# PHY_RJ45.net
KiCad netlist of a schematic drawn in Altium Designer
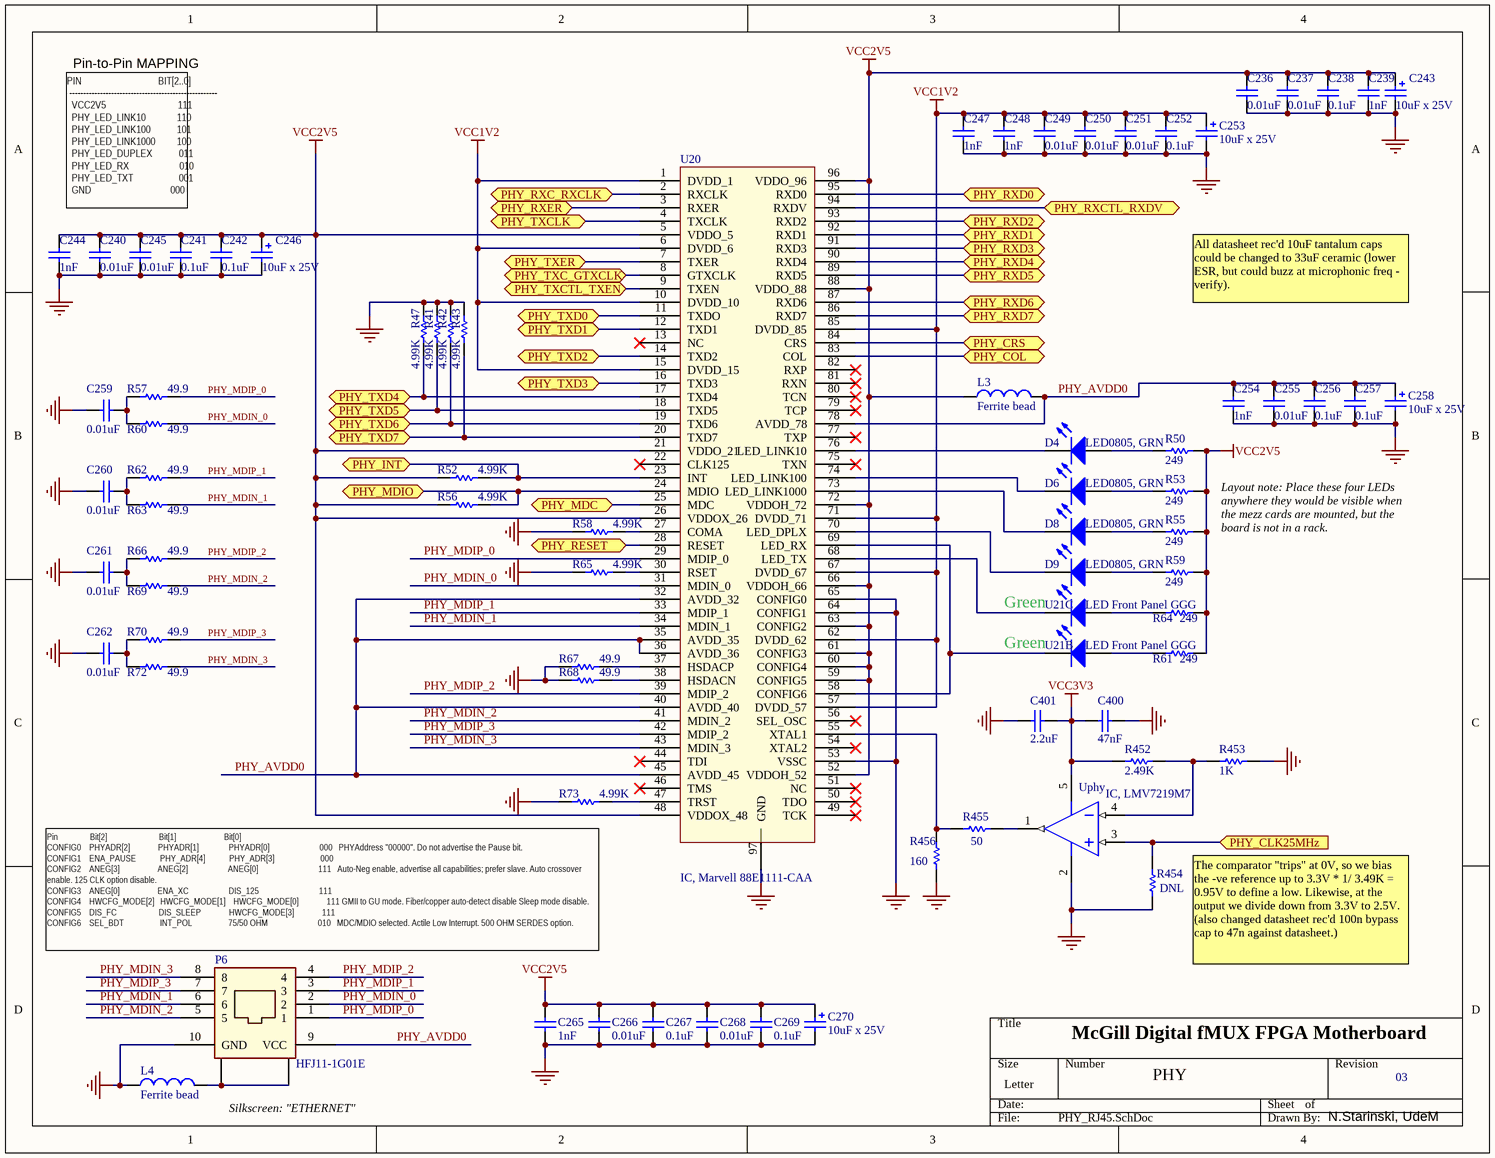
[diagram p0: PHY_RJ45.SchDoc]

(export (version "E")
  (design (tool "Eeschema 10.0.6"))
  (components
    (comp (ref "C236")
      (value "0.01uF")
      (footprint "CC1005-0402")
      (description "Capacitor (Semiconductor SIM Model)")
      (fields (field (name "PUBLISHER") "Altium Limited"))
      (libsource (lib "Miscellaneous Devices") (part "Cap Semi"))
    )
    (comp (ref "C237")
      (value "0.01uF")
      (footprint "CC1005-0402")
      (description "Capacitor (Semiconductor SIM Model)")
      (fields (field (name "PUBLISHER") "Altium Limited"))
      (libsource (lib "Miscellaneous Devices") (part "Cap Semi"))
    )
    (comp (ref "C238")
      (value "0.1uF")
      (footprint "CC1608-0603")
      (description "Capacitor (Semiconductor SIM Model)")
      (fields (field (name "PUBLISHER") "Altium Limited"))
      (libsource (lib "Miscellaneous Devices") (part "Cap Semi"))
    )
    (comp (ref "C239")
      (value "1nF")
      (footprint "CC1005-0402")
      (description "Capacitor (Semiconductor SIM Model)")
      (fields (field (name "PUBLISHER") "Altium Limited"))
      (libsource (lib "Miscellaneous Devices") (part "Cap Semi"))
    )
    (comp (ref "C240")
      (value "0.01uF")
      (footprint "CC1005-0402")
      (description "Capacitor (Semiconductor SIM Model)")
      (fields (field (name "PUBLISHER") "Altium Limited"))
      (libsource (lib "Miscellaneous Devices") (part "Cap Semi"))
    )
    (comp (ref "C241")
      (value "0.1uF")
      (footprint "CC1608-0603")
      (description "Capacitor (Semiconductor SIM Model)")
      (fields (field (name "PUBLISHER") "Altium Limited"))
      (libsource (lib "Miscellaneous Devices") (part "Cap Semi"))
    )
    (comp (ref "C242")
      (value "0.1uF")
      (footprint "CC1608-0603")
      (description "Capacitor (Semiconductor SIM Model)")
      (fields (field (name "PUBLISHER") "Altium Limited"))
      (libsource (lib "Miscellaneous Devices") (part "Cap Semi"))
    )
    (comp (ref "C243")
      (value "10uF x 25V")
      (footprint "TC6032-2412")
      (description "CAP POL B45197A5106K309")
      (fields (field (name "PUBLISHER") "Altium Limited"))
      (libsource (lib "Miscellaneous Devices 02") (part "Cap Pol3"))
    )
    (comp (ref "C244")
      (value "1nF")
      (footprint "CC1005-0402")
      (description "Capacitor (Semiconductor SIM Model)")
      (fields (field (name "PUBLISHER") "Altium Limited"))
      (libsource (lib "Miscellaneous Devices") (part "Cap Semi"))
    )
    (comp (ref "C245")
      (value "0.01uF")
      (footprint "CC1005-0402")
      (description "Capacitor (Semiconductor SIM Model)")
      (fields (field (name "PUBLISHER") "Altium Limited"))
      (libsource (lib "Miscellaneous Devices") (part "Cap Semi"))
    )
    (comp (ref "C246")
      (value "10uF x 25V")
      (footprint "TC6032-2412")
      (description "CAP POL B45197A5106K309")
      (fields (field (name "PUBLISHER") "Altium Limited"))
      (libsource (lib "Miscellaneous Devices 02") (part "Cap Pol3"))
    )
    (comp (ref "C247")
      (value "1nF")
      (footprint "CC1005-0402")
      (description "Capacitor (Semiconductor SIM Model)")
      (fields (field (name "PUBLISHER") "Altium Limited"))
      (libsource (lib "Miscellaneous Devices") (part "Cap Semi"))
    )
    (comp (ref "C248")
      (value "1nF")
      (footprint "CC1005-0402")
      (description "Capacitor (Semiconductor SIM Model)")
      (fields (field (name "PUBLISHER") "Altium Limited"))
      (libsource (lib "Miscellaneous Devices") (part "Cap Semi"))
    )
    (comp (ref "C249")
      (value "0.01uF")
      (footprint "CC1005-0402")
      (description "Capacitor (Semiconductor SIM Model)")
      (fields (field (name "PUBLISHER") "Altium Limited"))
      (libsource (lib "Miscellaneous Devices") (part "Cap Semi"))
    )
    (comp (ref "C250")
      (value "0.01uF")
      (footprint "CC1005-0402")
      (description "Capacitor (Semiconductor SIM Model)")
      (fields (field (name "PUBLISHER") "Altium Limited"))
      (libsource (lib "Miscellaneous Devices") (part "Cap Semi"))
    )
    (comp (ref "C251")
      (value "0.01uF")
      (footprint "CC1005-0402")
      (description "Capacitor (Semiconductor SIM Model)")
      (fields (field (name "PUBLISHER") "Altium Limited"))
      (libsource (lib "Miscellaneous Devices") (part "Cap Semi"))
    )
    (comp (ref "C252")
      (value "0.1uF")
      (footprint "CC1608-0603")
      (description "Capacitor (Semiconductor SIM Model)")
      (fields (field (name "PUBLISHER") "Altium Limited"))
      (libsource (lib "Miscellaneous Devices") (part "Cap Semi"))
    )
    (comp (ref "C253")
      (value "10uF x 25V")
      (footprint "TC6032-2412")
      (description "CAP POL B45197A5106K309")
      (fields (field (name "PUBLISHER") "Altium Limited"))
      (libsource (lib "Miscellaneous Devices 02") (part "Cap Pol3"))
    )
    (comp (ref "C254")
      (value "1nF")
      (footprint "CC1005-0402")
      (description "Capacitor (Semiconductor SIM Model)")
      (fields (field (name "PUBLISHER") "Altium Limited"))
      (libsource (lib "Miscellaneous Devices") (part "Cap Semi"))
    )
    (comp (ref "C255")
      (value "0.01uF")
      (footprint "CC1005-0402")
      (description "Capacitor (Semiconductor SIM Model)")
      (fields (field (name "PUBLISHER") "Altium Limited"))
      (libsource (lib "Miscellaneous Devices") (part "Cap Semi"))
    )
    (comp (ref "C256")
      (value "0.1uF")
      (footprint "CC1608-0603")
      (description "Capacitor (Semiconductor SIM Model)")
      (fields (field (name "PUBLISHER") "Altium Limited"))
      (libsource (lib "Miscellaneous Devices") (part "Cap Semi"))
    )
    (comp (ref "C257")
      (value "0.1uF")
      (footprint "CC1608-0603")
      (description "Capacitor (Semiconductor SIM Model)")
      (fields (field (name "PUBLISHER") "Altium Limited"))
      (libsource (lib "Miscellaneous Devices") (part "Cap Semi"))
    )
    (comp (ref "C258")
      (value "10uF x 25V")
      (footprint "TC6032-2412")
      (description "CAP POL B45197A5106K309")
      (fields (field (name "PUBLISHER") "Altium Limited"))
      (libsource (lib "Miscellaneous Devices 02") (part "Cap Pol3"))
    )
    (comp (ref "C259")
      (value "0.01uF")
      (footprint "CC1608-0603")
      (description "Capacitor (Semiconductor SIM Model)")
      (fields (field (name "PUBLISHER") "Altium Limited"))
      (libsource (lib "Miscellaneous Devices") (part "Cap Semi"))
    )
    (comp (ref "C260")
      (value "0.01uF")
      (footprint "CC1608-0603")
      (description "Capacitor (Semiconductor SIM Model)")
      (fields (field (name "PUBLISHER") "Altium Limited"))
      (libsource (lib "Miscellaneous Devices") (part "Cap Semi"))
    )
    (comp (ref "C261")
      (value "0.01uF")
      (footprint "CC1608-0603")
      (description "Capacitor (Semiconductor SIM Model)")
      (fields (field (name "PUBLISHER") "Altium Limited"))
      (libsource (lib "Miscellaneous Devices") (part "Cap Semi"))
    )
    (comp (ref "C262")
      (value "0.01uF")
      (footprint "CC1608-0603")
      (description "Capacitor (Semiconductor SIM Model)")
      (fields (field (name "PUBLISHER") "Altium Limited"))
      (libsource (lib "Miscellaneous Devices") (part "Cap Semi"))
    )
    (comp (ref "C265")
      (value "1nF")
      (footprint "CC1005-0402")
      (description "Capacitor (Semiconductor SIM Model)")
      (fields (field (name "PUBLISHER") "Altium Limited"))
      (libsource (lib "Miscellaneous Devices") (part "Cap Semi"))
    )
    (comp (ref "C266")
      (value "0.01uF")
      (footprint "CC1005-0402")
      (description "Capacitor (Semiconductor SIM Model)")
      (fields (field (name "PUBLISHER") "Altium Limited"))
      (libsource (lib "Miscellaneous Devices") (part "Cap Semi"))
    )
    (comp (ref "C267")
      (value "0.1uF")
      (footprint "CC1608-0603")
      (description "Capacitor (Semiconductor SIM Model)")
      (fields (field (name "PUBLISHER") "Altium Limited"))
      (libsource (lib "Miscellaneous Devices") (part "Cap Semi"))
    )
    (comp (ref "C268")
      (value "0.01uF")
      (footprint "CC1005-0402")
      (description "Capacitor (Semiconductor SIM Model)")
      (fields (field (name "PUBLISHER") "Altium Limited"))
      (libsource (lib "Miscellaneous Devices") (part "Cap Semi"))
    )
    (comp (ref "C269")
      (value "0.1uF")
      (footprint "CC1608-0603")
      (description "Capacitor (Semiconductor SIM Model)")
      (fields (field (name "PUBLISHER") "Altium Limited"))
      (libsource (lib "Miscellaneous Devices") (part "Cap Semi"))
    )
    (comp (ref "C270")
      (value "10uF x 25V")
      (footprint "TC6032-2412")
      (description "CAP POL B45197A5106K309")
      (fields (field (name "PUBLISHER") "Altium Limited"))
      (libsource (lib "Miscellaneous Devices 02") (part "Cap Pol3"))
    )
    (comp (ref "C400")
      (value "47nF")
      (footprint "CC1005-0402")
      (description "Capacitor (Semiconductor SIM Model)")
      (fields (field (name "PUBLISHER") "Altium Limited"))
      (libsource (lib "Miscellaneous Devices") (part "Cap Semi"))
    )
    (comp (ref "C401")
      (value "2.2uF")
      (footprint "CC3225-1210")
      (description "Capacitor (use 1206 footprint)")
      (fields (field (name "PUBLISHER") "Altium Limited"))
      (libsource (lib "Miscellaneous Devices") (part "Cap Semi"))
    )
    (comp (ref "D4")
      (value "LED0805, GRN")
      (footprint "SMD _LED")
      (description "LED 0805 LTST-C170GKT")
      (fields (field (name "PUBLISHER") "Altium Limited"))
      (libsource (lib "Miscellaneous Devices") (part "LED3"))
    )
    (comp (ref "D6")
      (value "LED0805, GRN")
      (footprint "SMD _LED")
      (description "LED 0805 LTST-C170GKT")
      (fields (field (name "PUBLISHER") "Altium Limited"))
      (libsource (lib "Miscellaneous Devices") (part "LED3"))
    )
    (comp (ref "D8")
      (value "LED0805, GRN")
      (footprint "SMD _LED")
      (description "LED 0805 LTST-C170GKT")
      (fields (field (name "PUBLISHER") "Altium Limited"))
      (libsource (lib "Miscellaneous Devices") (part "LED3"))
    )
    (comp (ref "D9")
      (value "LED0805, GRN")
      (footprint "SMD _LED")
      (description "LED 0805 LTST-C170GKT")
      (fields (field (name "PUBLISHER") "Altium Limited"))
      (libsource (lib "Miscellaneous Devices") (part "LED3"))
    )
    (comp (ref "L3")
      (value "Ferrite bead")
      (footprint "INDC2012-0805")
      (description "Inductor SM 0805")
      (fields (field (name "PUBLISHER") "Altium Limited"))
      (libsource (lib "Miscellaneous Devices") (part "Inductor"))
    )
    (comp (ref "L4")
      (value "Ferrite bead")
      (footprint "INDC2012-0805")
      (description "Inductor SM 0805")
      (fields (field (name "PUBLISHER") "Altium Limited"))
      (libsource (lib "Miscellaneous Devices 02") (part "Inductor"))
    )
    (comp (ref "P6")
      (value "HFJ11-1G01E")
      (footprint "HALO_RJ45")
      (description "Gigabit HALO RJ45")
      (libsource (lib "MyComp1") (part "HFJ11-1G01E"))
    )
    (comp (ref "R41")
      (value "4.99K")
      (footprint "CR1608-0603")
      (description "Resistor 0603")
      (fields (field (name "PUBLISHER") "Altium Limited"))
      (libsource (lib "Miscellaneous Devices") (part "Res Semi"))
    )
    (comp (ref "R42")
      (value "4.99K")
      (footprint "CR1608-0603")
      (description "Resistor 0603")
      (fields (field (name "PUBLISHER") "Altium Limited"))
      (libsource (lib "Miscellaneous Devices") (part "Res Semi"))
    )
    (comp (ref "R43")
      (value "4.99K")
      (footprint "CR1608-0603")
      (description "Resistor 0603")
      (fields (field (name "PUBLISHER") "Altium Limited"))
      (libsource (lib "Miscellaneous Devices") (part "Res Semi"))
    )
    (comp (ref "R47")
      (value "4.99K")
      (footprint "CR1608-0603")
      (description "Resistor 0603")
      (fields (field (name "PUBLISHER") "Altium Limited"))
      (libsource (lib "Miscellaneous Devices") (part "Res Semi"))
    )
    (comp (ref "R50")
      (value "249")
      (footprint "CR1608-0603")
      (description "Resistor 0603")
      (fields (field (name "PUBLISHER") "Altium Limited"))
      (libsource (lib "Miscellaneous Devices") (part "Res Semi"))
    )
    (comp (ref "R52")
      (value "4.99K")
      (footprint "CR1608-0603")
      (description "Resistor 0603")
      (fields (field (name "PUBLISHER") "Altium Limited"))
      (libsource (lib "Miscellaneous Devices") (part "Res Semi"))
    )
    (comp (ref "R53")
      (value "249")
      (footprint "CR1608-0603")
      (description "Resistor 0603")
      (fields (field (name "PUBLISHER") "Altium Limited"))
      (libsource (lib "Miscellaneous Devices") (part "Res Semi"))
    )
    (comp (ref "R55")
      (value "249")
      (footprint "CR1608-0603")
      (description "Resistor 0603")
      (fields (field (name "PUBLISHER") "Altium Limited"))
      (libsource (lib "Miscellaneous Devices") (part "Res Semi"))
    )
    (comp (ref "R56")
      (value "4.99K")
      (footprint "CR1608-0603")
      (description "Resistor 0603")
      (fields (field (name "PUBLISHER") "Altium Limited"))
      (libsource (lib "Miscellaneous Devices") (part "Res Semi"))
    )
    (comp (ref "R57")
      (value "49.9")
      (footprint "CR1608-0603")
      (description "Resistor 0603")
      (fields (field (name "PUBLISHER") "Altium Limited"))
      (libsource (lib "Miscellaneous Devices") (part "Res Semi"))
    )
    (comp (ref "R58")
      (value "4.99K")
      (footprint "CR1608-0603")
      (description "Resistor 0603")
      (fields (field (name "PUBLISHER") "Altium Limited"))
      (libsource (lib "Miscellaneous Devices") (part "Res Semi"))
    )
    (comp (ref "R59")
      (value "249")
      (footprint "CR1608-0603")
      (description "Resistor 0603")
      (fields (field (name "PUBLISHER") "Altium Limited"))
      (libsource (lib "Miscellaneous Devices") (part "Res Semi"))
    )
    (comp (ref "R60")
      (value "49.9")
      (footprint "CR1608-0603")
      (description "Resistor 0603")
      (fields (field (name "PUBLISHER") "Altium Limited"))
      (libsource (lib "Miscellaneous Devices") (part "Res Semi"))
    )
    (comp (ref "R61")
      (value "249")
      (footprint "CR1608-0603")
      (description "Resistor 0603")
      (fields (field (name "PUBLISHER") "Altium Limited"))
      (libsource (lib "Miscellaneous Devices") (part "Res Semi"))
    )
    (comp (ref "R62")
      (value "49.9")
      (footprint "CR1608-0603")
      (description "Resistor 0603")
      (fields (field (name "PUBLISHER") "Altium Limited"))
      (libsource (lib "Miscellaneous Devices") (part "Res Semi"))
    )
    (comp (ref "R63")
      (value "49.9")
      (footprint "CR1608-0603")
      (description "Resistor 0603")
      (fields (field (name "PUBLISHER") "Altium Limited"))
      (libsource (lib "Miscellaneous Devices") (part "Res Semi"))
    )
    (comp (ref "R64")
      (value "249")
      (footprint "CR1608-0603")
      (description "Resistor 0603")
      (fields (field (name "PUBLISHER") "Altium Limited"))
      (libsource (lib "Miscellaneous Devices") (part "Res Semi"))
    )
    (comp (ref "R65")
      (value "4.99K")
      (footprint "CR1608-0603")
      (description "Resistor 0603")
      (fields (field (name "PUBLISHER") "Altium Limited"))
      (libsource (lib "Miscellaneous Devices") (part "Res Semi"))
    )
    (comp (ref "R66")
      (value "49.9")
      (footprint "CR1608-0603")
      (description "Resistor 0603")
      (fields (field (name "PUBLISHER") "Altium Limited"))
      (libsource (lib "Miscellaneous Devices") (part "Res Semi"))
    )
    (comp (ref "R67")
      (value "49.9")
      (footprint "CR1608-0603")
      (description "Resistor 0603")
      (fields (field (name "PUBLISHER") "Altium Limited"))
      (libsource (lib "Miscellaneous Devices") (part "Res Semi"))
    )
    (comp (ref "R68")
      (value "49.9")
      (footprint "CR1608-0603")
      (description "Resistor 0603")
      (fields (field (name "PUBLISHER") "Altium Limited"))
      (libsource (lib "Miscellaneous Devices") (part "Res Semi"))
    )
    (comp (ref "R69")
      (value "49.9")
      (footprint "CR1608-0603")
      (description "Resistor 0603")
      (fields (field (name "PUBLISHER") "Altium Limited"))
      (libsource (lib "Miscellaneous Devices") (part "Res Semi"))
    )
    (comp (ref "R70")
      (value "49.9")
      (footprint "CR1608-0603")
      (description "Resistor 0603")
      (fields (field (name "PUBLISHER") "Altium Limited"))
      (libsource (lib "Miscellaneous Devices") (part "Res Semi"))
    )
    (comp (ref "R72")
      (value "49.9")
      (footprint "CR1608-0603")
      (description "Resistor 0603")
      (fields (field (name "PUBLISHER") "Altium Limited"))
      (libsource (lib "Miscellaneous Devices") (part "Res Semi"))
    )
    (comp (ref "R73")
      (value "4.99K")
      (footprint "CR1608-0603")
      (description "Resistor 0603")
      (fields (field (name "PUBLISHER") "Altium Limited"))
      (libsource (lib "Miscellaneous Devices") (part "Res Semi"))
    )
    (comp (ref "R452")
      (value "2.49K")
      (footprint "CR1608-0603")
      (description "Resistor 0603")
      (fields (field (name "PUBLISHER") "Altium Limited"))
      (libsource (lib "Miscellaneous Devices") (part "Res Semi"))
    )
    (comp (ref "R453")
      (value "1K")
      (footprint "CR1608-0603")
      (description "Resistor 0603")
      (fields (field (name "PUBLISHER") "Altium Limited"))
      (libsource (lib "Miscellaneous Devices") (part "Res Semi"))
    )
    (comp (ref "R454")
      (value "DNL")
      (footprint "CR1608-0603")
      (description "Semiconductor Resistor")
      (fields (field (name "PUBLISHER") "Altium Limited"))
      (libsource (lib "Miscellaneous Devices") (part "Res Semi"))
    )
    (comp (ref "R455")
      (value "50")
      (footprint "CR1608-0603")
      (description "Resistor 0603")
      (fields (field (name "PUBLISHER") "Altium Limited"))
      (libsource (lib "Miscellaneous Devices") (part "Res Semi"))
    )
    (comp (ref "R456")
      (value "160")
      (footprint "CR1608-0603")
      (description "Resistor 0603")
      (fields (field (name "PUBLISHER") "Altium Limited"))
      (libsource (lib "Miscellaneous Devices") (part "Res Semi"))
    )
    (comp (ref "U20")
      (value "IC, Marvell 88E1111-CAA")
      (footprint "BCC_96")
      (description "PHY 10/100/1000 Alaska Single-Port Gigabit Transceiver")
      (libsource (lib "MyComp1") (part "M88E1111-CAA"))
    )
    (comp (ref "U21")
      (value "LED Front Panel GGG")
      (footprint "LED_Tri_")
      (description "564-0200-222F")
      (libsource (lib "Miscellaneous Devices 02") (part "LED_Tri"))
    )
    (comp (ref "Uphy")
      (value "IC, LMV7219M7")
      (footprint "MAA05A")
      (description "Voltage Comparator")
      (libsource (lib "NSC Analog Comparator") (part "LMV7219"))
    )
  )
  (nets
    (net (code "1") (name "/PHY_AVDD0") (class "Default")
      (node (ref "C254") (pin "2") (pinfunction "2_2") (pintype "passive"))
      (node (ref "C255") (pin "2") (pinfunction "2_2") (pintype "passive"))
      (node (ref "C256") (pin "2") (pinfunction "2_2") (pintype "passive"))
      (node (ref "C257") (pin "2") (pinfunction "2_2") (pintype "passive"))
      (node (ref "C258") (pin "1") (pinfunction "1_1") (pintype "passive"))
      (node (ref "L3") (pin "2") (pinfunction "2_2") (pintype "passive"))
      (node (ref "P6") (pin "9") (pinfunction "VCC_9") (pintype "passive"))
      (node (ref "U20") (pin "32") (pinfunction "AVDD_32_32") (pintype "passive"))
      (node (ref "U20") (pin "35") (pinfunction "AVDD_35_35") (pintype "passive"))
      (node (ref "U20") (pin "36") (pinfunction "AVDD_36_36") (pintype "passive"))
      (node (ref "U20") (pin "40") (pinfunction "AVDD_40_40") (pintype "passive"))
      (node (ref "U20") (pin "45") (pinfunction "AVDD_45_45") (pintype "passive"))
      (node (ref "U20") (pin "78") (pinfunction "AVDD_78_78") (pintype "passive"))
    )
    (net (code "2") (name "/PHY_CLK25MHz") (class "Default")
      (node (ref "R454") (pin "2") (pinfunction "2_2") (pintype "passive"))
      (node (ref "Uphy") (pin "3") (pinfunction "IN+_3") (pintype "input"))
    )
    (net (code "3") (name "/PHY_COL") (class "Default")
      (node (ref "U20") (pin "83") (pinfunction "COL_83") (pintype "passive"))
    )
    (net (code "4") (name "/PHY_CRS") (class "Default")
      (node (ref "U20") (pin "84") (pinfunction "CRS_84") (pintype "passive"))
    )
    (net (code "5") (name "/PHY_INT") (class "Default")
      (node (ref "R52") (pin "2") (pinfunction "2_2") (pintype "passive"))
      (node (ref "U20") (pin "23") (pinfunction "INT_23") (pintype "passive"))
    )
    (net (code "6") (name "/PHY_MDC") (class "Default")
      (node (ref "U20") (pin "25") (pinfunction "MDC_25") (pintype "passive"))
    )
    (net (code "7") (name "/PHY_MDIN_0") (class "Default")
      (node (ref "P6") (pin "2") (pinfunction "2_2") (pintype "passive"))
      (node (ref "R60") (pin "2") (pinfunction "2_2") (pintype "passive"))
      (node (ref "U20") (pin "31") (pinfunction "MDIN_0_31") (pintype "passive"))
    )
    (net (code "8") (name "/PHY_MDIN_1") (class "Default")
      (node (ref "P6") (pin "6") (pinfunction "6_6") (pintype "passive"))
      (node (ref "R63") (pin "2") (pinfunction "2_2") (pintype "passive"))
      (node (ref "U20") (pin "34") (pinfunction "MDIN_1_34") (pintype "passive"))
    )
    (net (code "9") (name "/PHY_MDIN_2") (class "Default")
      (node (ref "P6") (pin "5") (pinfunction "5_5") (pintype "passive"))
      (node (ref "R69") (pin "2") (pinfunction "2_2") (pintype "passive"))
      (node (ref "U20") (pin "41") (pinfunction "MDIN_2_41") (pintype "passive"))
    )
    (net (code "10") (name "/PHY_MDIN_3") (class "Default")
      (node (ref "P6") (pin "8") (pinfunction "8_8") (pintype "passive"))
      (node (ref "R72") (pin "2") (pinfunction "2_2") (pintype "passive"))
      (node (ref "U20") (pin "43") (pinfunction "MDIN_3_43") (pintype "passive"))
    )
    (net (code "11") (name "/PHY_MDIO") (class "Default")
      (node (ref "R56") (pin "2") (pinfunction "2_2") (pintype "passive"))
      (node (ref "U20") (pin "24") (pinfunction "MDIO_24") (pintype "passive"))
    )
    (net (code "12") (name "/PHY_MDIP_0") (class "Default")
      (node (ref "P6") (pin "1") (pinfunction "1_1") (pintype "passive"))
      (node (ref "R57") (pin "2") (pinfunction "2_2") (pintype "passive"))
      (node (ref "U20") (pin "29") (pinfunction "MDIP_0_29") (pintype "passive"))
    )
    (net (code "13") (name "/PHY_MDIP_1") (class "Default")
      (node (ref "P6") (pin "3") (pinfunction "3_3") (pintype "passive"))
      (node (ref "R62") (pin "2") (pinfunction "2_2") (pintype "passive"))
      (node (ref "U20") (pin "33") (pinfunction "MDIP_1_33") (pintype "passive"))
    )
    (net (code "14") (name "/PHY_MDIP_2") (class "Default")
      (node (ref "P6") (pin "4") (pinfunction "4_4") (pintype "passive"))
      (node (ref "R66") (pin "2") (pinfunction "2_2") (pintype "passive"))
      (node (ref "U20") (pin "39") (pinfunction "MDIP_2_39") (pintype "passive"))
    )
    (net (code "15") (name "/PHY_MDIP_3") (class "Default")
      (node (ref "P6") (pin "7") (pinfunction "7_7") (pintype "passive"))
      (node (ref "R70") (pin "2") (pinfunction "2_2") (pintype "passive"))
      (node (ref "U20") (pin "42") (pinfunction "MDIP_2_42") (pintype "passive"))
    )
    (net (code "16") (name "/PHY_RESET") (class "Default")
      (node (ref "U20") (pin "28") (pinfunction "RESET_28") (pintype "passive"))
    )
    (net (code "17") (name "/PHY_RXCTL_RXDV") (class "Default")
      (node (ref "U20") (pin "94") (pinfunction "RXDV_94") (pintype "passive"))
    )
    (net (code "18") (name "/PHY_RXC_RXCLK") (class "Default")
      (node (ref "U20") (pin "2") (pinfunction "RXCLK_2") (pintype "passive"))
    )
    (net (code "19") (name "/PHY_RXD0") (class "Default")
      (node (ref "U20") (pin "95") (pinfunction "RXD0_95") (pintype "passive"))
    )
    (net (code "20") (name "/PHY_RXD1") (class "Default")
      (node (ref "U20") (pin "92") (pinfunction "RXD1_92") (pintype "passive"))
    )
    (net (code "21") (name "/PHY_RXD2") (class "Default")
      (node (ref "U20") (pin "93") (pinfunction "RXD2_93") (pintype "passive"))
    )
    (net (code "22") (name "/PHY_RXD3") (class "Default")
      (node (ref "U20") (pin "91") (pinfunction "RXD3_91") (pintype "passive"))
    )
    (net (code "23") (name "/PHY_RXD4") (class "Default")
      (node (ref "U20") (pin "90") (pinfunction "RXD4_90") (pintype "passive"))
    )
    (net (code "24") (name "/PHY_RXD5") (class "Default")
      (node (ref "U20") (pin "89") (pinfunction "RXD5_89") (pintype "passive"))
    )
    (net (code "25") (name "/PHY_RXD6") (class "Default")
      (node (ref "U20") (pin "87") (pinfunction "RXD6_87") (pintype "passive"))
    )
    (net (code "26") (name "/PHY_RXD7") (class "Default")
      (node (ref "U20") (pin "86") (pinfunction "RXD7_86") (pintype "passive"))
    )
    (net (code "27") (name "/PHY_RXER") (class "Default")
      (node (ref "U20") (pin "3") (pinfunction "RXER_3") (pintype "passive"))
    )
    (net (code "28") (name "/PHY_TXCLK") (class "Default")
      (node (ref "U20") (pin "4") (pinfunction "TXCLK_4") (pintype "passive"))
    )
    (net (code "29") (name "/PHY_TXCTL_TXEN") (class "Default")
      (node (ref "U20") (pin "9") (pinfunction "TXEN_9") (pintype "passive"))
    )
    (net (code "30") (name "/PHY_TXC_GTXCLK") (class "Default")
      (node (ref "U20") (pin "8") (pinfunction "GTXCLK_8") (pintype "passive"))
    )
    (net (code "31") (name "/PHY_TXD0") (class "Default")
      (node (ref "U20") (pin "11") (pinfunction "TXDO_11") (pintype "passive"))
    )
    (net (code "32") (name "/PHY_TXD1") (class "Default")
      (node (ref "U20") (pin "12") (pinfunction "TXD1_12") (pintype "passive"))
    )
    (net (code "33") (name "/PHY_TXD2") (class "Default")
      (node (ref "U20") (pin "14") (pinfunction "TXD2_14") (pintype "passive"))
    )
    (net (code "34") (name "/PHY_TXD3") (class "Default")
      (node (ref "U20") (pin "16") (pinfunction "TXD3_16") (pintype "passive"))
    )
    (net (code "35") (name "/PHY_TXD4") (class "Default")
      (node (ref "R47") (pin "1") (pinfunction "1_1") (pintype "passive"))
      (node (ref "U20") (pin "17") (pinfunction "TXD4_17") (pintype "passive"))
    )
    (net (code "36") (name "/PHY_TXD5") (class "Default")
      (node (ref "R41") (pin "1") (pinfunction "1_1") (pintype "passive"))
      (node (ref "U20") (pin "18") (pinfunction "TXD5_18") (pintype "passive"))
    )
    (net (code "37") (name "/PHY_TXD6") (class "Default")
      (node (ref "R42") (pin "1") (pinfunction "1_1") (pintype "passive"))
      (node (ref "U20") (pin "19") (pinfunction "TXD6_19") (pintype "passive"))
    )
    (net (code "38") (name "/PHY_TXD7") (class "Default")
      (node (ref "R43") (pin "1") (pinfunction "1_1") (pintype "passive"))
      (node (ref "U20") (pin "20") (pinfunction "TXD7_20") (pintype "passive"))
    )
    (net (code "39") (name "/PHY_TXER") (class "Default")
      (node (ref "U20") (pin "7") (pinfunction "TXER_7") (pintype "passive"))
    )
    (net (code "40") (name "GND") (class "Default")
      (node (ref "C236") (pin "1") (pinfunction "1_1") (pintype "passive"))
      (node (ref "C237") (pin "1") (pinfunction "1_1") (pintype "passive"))
      (node (ref "C238") (pin "1") (pinfunction "1_1") (pintype "passive"))
      (node (ref "C239") (pin "1") (pinfunction "1_1") (pintype "passive"))
      (node (ref "C240") (pin "1") (pinfunction "1_1") (pintype "passive"))
      (node (ref "C241") (pin "1") (pinfunction "1_1") (pintype "passive"))
      (node (ref "C242") (pin "1") (pinfunction "1_1") (pintype "passive"))
      (node (ref "C243") (pin "2") (pinfunction "2_2") (pintype "passive"))
      (node (ref "C244") (pin "1") (pinfunction "1_1") (pintype "passive"))
      (node (ref "C245") (pin "1") (pinfunction "1_1") (pintype "passive"))
      (node (ref "C246") (pin "2") (pinfunction "2_2") (pintype "passive"))
      (node (ref "C247") (pin "1") (pinfunction "1_1") (pintype "passive"))
      (node (ref "C248") (pin "1") (pinfunction "1_1") (pintype "passive"))
      (node (ref "C249") (pin "1") (pinfunction "1_1") (pintype "passive"))
      (node (ref "C250") (pin "1") (pinfunction "1_1") (pintype "passive"))
      (node (ref "C251") (pin "1") (pinfunction "1_1") (pintype "passive"))
      (node (ref "C252") (pin "1") (pinfunction "1_1") (pintype "passive"))
      (node (ref "C253") (pin "2") (pinfunction "2_2") (pintype "passive"))
      (node (ref "C254") (pin "1") (pinfunction "1_1") (pintype "passive"))
      (node (ref "C255") (pin "1") (pinfunction "1_1") (pintype "passive"))
      (node (ref "C256") (pin "1") (pinfunction "1_1") (pintype "passive"))
      (node (ref "C257") (pin "1") (pinfunction "1_1") (pintype "passive"))
      (node (ref "C258") (pin "2") (pinfunction "2_2") (pintype "passive"))
      (node (ref "C259") (pin "1") (pinfunction "1_1") (pintype "passive"))
      (node (ref "C260") (pin "1") (pinfunction "1_1") (pintype "passive"))
      (node (ref "C261") (pin "1") (pinfunction "1_1") (pintype "passive"))
      (node (ref "C262") (pin "1") (pinfunction "1_1") (pintype "passive"))
      (node (ref "C265") (pin "1") (pinfunction "1_1") (pintype "passive"))
      (node (ref "C266") (pin "1") (pinfunction "1_1") (pintype "passive"))
      (node (ref "C267") (pin "1") (pinfunction "1_1") (pintype "passive"))
      (node (ref "C268") (pin "1") (pinfunction "1_1") (pintype "passive"))
      (node (ref "C269") (pin "1") (pinfunction "1_1") (pintype "passive"))
      (node (ref "C270") (pin "2") (pinfunction "2_2") (pintype "passive"))
      (node (ref "C400") (pin "2") (pinfunction "2_2") (pintype "passive"))
      (node (ref "C401") (pin "2") (pinfunction "2_2") (pintype "passive"))
      (node (ref "L4") (pin "1") (pinfunction "1_1") (pintype "passive"))
      (node (ref "P6") (pin "10") (pinfunction "GND_10") (pintype "passive"))
      (node (ref "R41") (pin "2") (pinfunction "2_2") (pintype "passive"))
      (node (ref "R42") (pin "2") (pinfunction "2_2") (pintype "passive"))
      (node (ref "R43") (pin "2") (pinfunction "2_2") (pintype "passive"))
      (node (ref "R453") (pin "2") (pinfunction "2_2") (pintype "passive"))
      (node (ref "R454") (pin "1") (pinfunction "1_1") (pintype "passive"))
      (node (ref "R456") (pin "1") (pinfunction "1_1") (pintype "passive"))
      (node (ref "R47") (pin "2") (pinfunction "2_2") (pintype "passive"))
      (node (ref "R58") (pin "1") (pinfunction "1_1") (pintype "passive"))
      (node (ref "R65") (pin "1") (pinfunction "1_1") (pintype "passive"))
      (node (ref "R67") (pin "1") (pinfunction "1_1") (pintype "passive"))
      (node (ref "R68") (pin "1") (pinfunction "1_1") (pintype "passive"))
      (node (ref "R73") (pin "1") (pinfunction "1_1") (pintype "passive"))
      (node (ref "U20") (pin "53") (pinfunction "VSSC_53") (pintype "passive"))
      (node (ref "U20") (pin "64") (pinfunction "CONFIG1_64") (pintype "passive"))
      (node (ref "U20") (pin "65") (pinfunction "CONFIG0_65") (pintype "passive"))
      (node (ref "U20") (pin "97") (pinfunction "GND_97") (pintype "passive"))
      (node (ref "Uphy") (pin "2") (pinfunction "V-_2") (pintype "power_in"))
    )
    (net (code "41") (name "Net-(C259-Pad2)") (class "Default")
      (node (ref "C259") (pin "2") (pinfunction "2_2") (pintype "passive"))
      (node (ref "R57") (pin "1") (pinfunction "1_1") (pintype "passive"))
      (node (ref "R60") (pin "1") (pinfunction "1_1") (pintype "passive"))
    )
    (net (code "42") (name "Net-(C260-Pad2)") (class "Default")
      (node (ref "C260") (pin "2") (pinfunction "2_2") (pintype "passive"))
      (node (ref "R62") (pin "1") (pinfunction "1_1") (pintype "passive"))
      (node (ref "R63") (pin "1") (pinfunction "1_1") (pintype "passive"))
    )
    (net (code "43") (name "Net-(C261-Pad2)") (class "Default")
      (node (ref "C261") (pin "2") (pinfunction "2_2") (pintype "passive"))
      (node (ref "R66") (pin "1") (pinfunction "1_1") (pintype "passive"))
      (node (ref "R69") (pin "1") (pinfunction "1_1") (pintype "passive"))
    )
    (net (code "44") (name "Net-(C262-Pad2)") (class "Default")
      (node (ref "C262") (pin "2") (pinfunction "2_2") (pintype "passive"))
      (node (ref "R70") (pin "1") (pinfunction "1_1") (pintype "passive"))
      (node (ref "R72") (pin "1") (pinfunction "1_1") (pintype "passive"))
    )
    (net (code "45") (name "Net-(D4-A)") (class "Default")
      (node (ref "D4") (pin "1") (pinfunction "A_1") (pintype "passive"))
      (node (ref "R50") (pin "1") (pinfunction "1_1") (pintype "passive"))
    )
    (net (code "46") (name "Net-(D4-K)") (class "Default")
      (node (ref "D4") (pin "2") (pinfunction "K_2") (pintype "passive"))
      (node (ref "U20") (pin "76") (pinfunction "LED_LINK10_76") (pintype "passive"))
    )
    (net (code "47") (name "Net-(D6-A)") (class "Default")
      (node (ref "D6") (pin "1") (pinfunction "A_1") (pintype "passive"))
      (node (ref "R53") (pin "1") (pinfunction "1_1") (pintype "passive"))
    )
    (net (code "48") (name "Net-(D6-K)") (class "Default")
      (node (ref "D6") (pin "2") (pinfunction "K_2") (pintype "passive"))
      (node (ref "U20") (pin "74") (pinfunction "LED_LINK100_74") (pintype "passive"))
    )
    (net (code "49") (name "Net-(D8-A)") (class "Default")
      (node (ref "D8") (pin "1") (pinfunction "A_1") (pintype "passive"))
      (node (ref "R55") (pin "1") (pinfunction "1_1") (pintype "passive"))
    )
    (net (code "50") (name "Net-(D8-K)") (class "Default")
      (node (ref "D8") (pin "2") (pinfunction "K_2") (pintype "passive"))
      (node (ref "U20") (pin "73") (pinfunction "LED_LINK1000_73") (pintype "passive"))
    )
    (net (code "51") (name "Net-(D9-A)") (class "Default")
      (node (ref "D9") (pin "1") (pinfunction "A_1") (pintype "passive"))
      (node (ref "R59") (pin "1") (pinfunction "1_1") (pintype "passive"))
    )
    (net (code "52") (name "Net-(D9-K)") (class "Default")
      (node (ref "D9") (pin "2") (pinfunction "K_2") (pintype "passive"))
      (node (ref "U20") (pin "70") (pinfunction "LED_DPLX_70") (pintype "passive"))
    )
    (net (code "53") (name "Net-(L4-Pad2)") (class "Default")
      (node (ref "L4") (pin "2") (pinfunction "2_2") (pintype "passive"))
      (node (ref "P6") (pin "11") (pinfunction "GND_11") (pintype "power_in"))
      (node (ref "P6") (pin "12") (pinfunction "GND_12") (pintype "power_in"))
    )
    (net (code "54") (name "Net-(U20-COMA)") (class "Default")
      (node (ref "R58") (pin "2") (pinfunction "2_2") (pintype "passive"))
      (node (ref "U20") (pin "27") (pinfunction "COMA_27") (pintype "passive"))
    )
    (net (code "55") (name "Net-(U20-CONFIG6)") (class "Default")
      (node (ref "U20") (pin "58") (pinfunction "CONFIG6_58") (pintype "passive"))
      (node (ref "U20") (pin "69") (pinfunction "LED_RX_69") (pintype "passive"))
      (node (ref "U21") (pin "K2") (pinfunction "K_K2") (pintype "passive"))
    )
    (net (code "56") (name "Net-(U20-HSDACN)") (class "Default")
      (node (ref "R68") (pin "2") (pinfunction "2_2") (pintype "passive"))
      (node (ref "U20") (pin "38") (pinfunction "HSDACN_38") (pintype "passive"))
    )
    (net (code "57") (name "Net-(U20-HSDACP)") (class "Default")
      (node (ref "R67") (pin "2") (pinfunction "2_2") (pintype "passive"))
      (node (ref "U20") (pin "37") (pinfunction "HSDACP_37") (pintype "passive"))
    )
    (net (code "58") (name "Net-(U20-LED_TX)") (class "Default")
      (node (ref "U20") (pin "68") (pinfunction "LED_TX_68") (pintype "passive"))
      (node (ref "U21") (pin "K3") (pinfunction "K_K3") (pintype "passive"))
    )
    (net (code "59") (name "Net-(U20-RSET)") (class "Default")
      (node (ref "R65") (pin "2") (pinfunction "2_2") (pintype "passive"))
      (node (ref "U20") (pin "30") (pinfunction "RSET_30") (pintype "passive"))
    )
    (net (code "60") (name "Net-(U20-TRST)") (class "Default")
      (node (ref "R73") (pin "2") (pinfunction "2_2") (pintype "passive"))
      (node (ref "U20") (pin "47") (pinfunction "TRST_47") (pintype "passive"))
    )
    (net (code "61") (name "Net-(U20-XTAL1)") (class "Default")
      (node (ref "R455") (pin "1") (pinfunction "1_1") (pintype "passive"))
      (node (ref "R456") (pin "2") (pinfunction "2_2") (pintype "passive"))
      (node (ref "U20") (pin "55") (pinfunction "XTAL1_55") (pintype "passive"))
    )
    (net (code "62") (name "Net-(U21B-A)") (class "Default")
      (node (ref "R61") (pin "1") (pinfunction "1_1") (pintype "passive"))
      (node (ref "U21") (pin "A2") (pinfunction "A_A2") (pintype "passive"))
    )
    (net (code "63") (name "Net-(U21C-A)") (class "Default")
      (node (ref "R64") (pin "1") (pinfunction "1_1") (pintype "passive"))
      (node (ref "U21") (pin "A3") (pinfunction "A_A3") (pintype "passive"))
    )
    (net (code "64") (name "Net-(Uphy-IN-)") (class "Default")
      (node (ref "R452") (pin "2") (pinfunction "2_2") (pintype "passive"))
      (node (ref "R453") (pin "1") (pinfunction "1_1") (pintype "passive"))
      (node (ref "Uphy") (pin "4") (pinfunction "IN-_4") (pintype "input"))
    )
    (net (code "65") (name "Net-(Uphy-OUT)") (class "Default")
      (node (ref "R455") (pin "2") (pinfunction "2_2") (pintype "passive"))
      (node (ref "Uphy") (pin "1") (pinfunction "OUT_1") (pintype "output"))
    )
    (net (code "66") (name "VCC1V2") (class "Default")
      (node (ref "C247") (pin "2") (pinfunction "2_2") (pintype "passive"))
      (node (ref "C248") (pin "2") (pinfunction "2_2") (pintype "passive"))
      (node (ref "C249") (pin "2") (pinfunction "2_2") (pintype "passive"))
      (node (ref "C250") (pin "2") (pinfunction "2_2") (pintype "passive"))
      (node (ref "C251") (pin "2") (pinfunction "2_2") (pintype "passive"))
      (node (ref "C252") (pin "2") (pinfunction "2_2") (pintype "passive"))
      (node (ref "C253") (pin "1") (pinfunction "1_1") (pintype "passive"))
      (node (ref "U20") (pin "1") (pinfunction "DVDD_1_1") (pintype "passive"))
      (node (ref "U20") (pin "10") (pinfunction "DVDD_10_10") (pintype "passive"))
      (node (ref "U20") (pin "15") (pinfunction "DVDD_15_15") (pintype "passive"))
      (node (ref "U20") (pin "57") (pinfunction "DVDD_57_57") (pintype "passive"))
      (node (ref "U20") (pin "6") (pinfunction "DVDD_6_6") (pintype "passive"))
      (node (ref "U20") (pin "62") (pinfunction "DVDD_62_62") (pintype "passive"))
      (node (ref "U20") (pin "67") (pinfunction "DVDD_67_67") (pintype "passive"))
      (node (ref "U20") (pin "71") (pinfunction "DVDD_71_71") (pintype "passive"))
      (node (ref "U20") (pin "85") (pinfunction "DVDD_85_85") (pintype "passive"))
    )
    (net (code "67") (name "VCC2V5") (class "Default")
      (node (ref "C236") (pin "2") (pinfunction "2_2") (pintype "passive"))
      (node (ref "C237") (pin "2") (pinfunction "2_2") (pintype "passive"))
      (node (ref "C238") (pin "2") (pinfunction "2_2") (pintype "passive"))
      (node (ref "C239") (pin "2") (pinfunction "2_2") (pintype "passive"))
      (node (ref "C240") (pin "2") (pinfunction "2_2") (pintype "passive"))
      (node (ref "C241") (pin "2") (pinfunction "2_2") (pintype "passive"))
      (node (ref "C242") (pin "2") (pinfunction "2_2") (pintype "passive"))
      (node (ref "C243") (pin "1") (pinfunction "1_1") (pintype "passive"))
      (node (ref "C244") (pin "2") (pinfunction "2_2") (pintype "passive"))
      (node (ref "C245") (pin "2") (pinfunction "2_2") (pintype "passive"))
      (node (ref "C246") (pin "1") (pinfunction "1_1") (pintype "passive"))
      (node (ref "C265") (pin "2") (pinfunction "2_2") (pintype "passive"))
      (node (ref "C266") (pin "2") (pinfunction "2_2") (pintype "passive"))
      (node (ref "C267") (pin "2") (pinfunction "2_2") (pintype "passive"))
      (node (ref "C268") (pin "2") (pinfunction "2_2") (pintype "passive"))
      (node (ref "C269") (pin "2") (pinfunction "2_2") (pintype "passive"))
      (node (ref "C270") (pin "1") (pinfunction "1_1") (pintype "passive"))
      (node (ref "L3") (pin "1") (pinfunction "1_1") (pintype "passive"))
      (node (ref "R50") (pin "2") (pinfunction "2_2") (pintype "passive"))
      (node (ref "R52") (pin "1") (pinfunction "1_1") (pintype "passive"))
      (node (ref "R53") (pin "2") (pinfunction "2_2") (pintype "passive"))
      (node (ref "R55") (pin "2") (pinfunction "2_2") (pintype "passive"))
      (node (ref "R56") (pin "1") (pinfunction "1_1") (pintype "passive"))
      (node (ref "R59") (pin "2") (pinfunction "2_2") (pintype "passive"))
      (node (ref "R61") (pin "2") (pinfunction "2_2") (pintype "passive"))
      (node (ref "R64") (pin "2") (pinfunction "2_2") (pintype "passive"))
      (node (ref "U20") (pin "21") (pinfunction "VDDO_21_21") (pintype "passive"))
      (node (ref "U20") (pin "26") (pinfunction "VDDOX_26_26") (pintype "passive"))
      (node (ref "U20") (pin "48") (pinfunction "VDDOX_48_48") (pintype "passive"))
      (node (ref "U20") (pin "5") (pinfunction "VDDO_5_5") (pintype "passive"))
      (node (ref "U20") (pin "52") (pinfunction "VDDOH_52_52") (pintype "passive"))
      (node (ref "U20") (pin "59") (pinfunction "CONFIG5_59") (pintype "passive"))
      (node (ref "U20") (pin "60") (pinfunction "CONFIG4_60") (pintype "passive"))
      (node (ref "U20") (pin "61") (pinfunction "CONFIG3_61") (pintype "passive"))
      (node (ref "U20") (pin "63") (pinfunction "CONFIG2_63") (pintype "passive"))
      (node (ref "U20") (pin "66") (pinfunction "VDDOH_66_66") (pintype "passive"))
      (node (ref "U20") (pin "72") (pinfunction "VDDOH_72_72") (pintype "passive"))
      (node (ref "U20") (pin "88") (pinfunction "VDDO_88_88") (pintype "passive"))
      (node (ref "U20") (pin "96") (pinfunction "VDDO_96_96") (pintype "passive"))
    )
    (net (code "68") (name "VCC3V3") (class "Default")
      (node (ref "C400") (pin "1") (pinfunction "1_1") (pintype "passive"))
      (node (ref "C401") (pin "1") (pinfunction "1_1") (pintype "passive"))
      (node (ref "R452") (pin "1") (pinfunction "1_1") (pintype "passive"))
      (node (ref "Uphy") (pin "5") (pinfunction "V+_5") (pintype "power_in"))
    )
    (net (code "69") (name "unconnected-(U20-CLK125-Pad22)") (class "Default")
      (node (ref "U20") (pin "22") (pinfunction "CLK125_22") (pintype "passive+no_connect"))
    )
    (net (code "70") (name "unconnected-(U20-NC-Pad13)") (class "Default")
      (node (ref "U20") (pin "13") (pinfunction "NC_13") (pintype "passive+no_connect"))
    )
    (net (code "71") (name "unconnected-(U20-NC-Pad51)") (class "Default")
      (node (ref "U20") (pin "51") (pinfunction "NC_51") (pintype "passive+no_connect"))
    )
    (net (code "72") (name "unconnected-(U20-RXN-Pad81)") (class "Default")
      (node (ref "U20") (pin "81") (pinfunction "RXN_81") (pintype "passive+no_connect"))
    )
    (net (code "73") (name "unconnected-(U20-RXP-Pad82)") (class "Default")
      (node (ref "U20") (pin "82") (pinfunction "RXP_82") (pintype "passive+no_connect"))
    )
    (net (code "74") (name "unconnected-(U20-SEL_OSC-Pad56)") (class "Default")
      (node (ref "U20") (pin "56") (pinfunction "SEL_OSC_56") (pintype "passive+no_connect"))
    )
    (net (code "75") (name "unconnected-(U20-TCK-Pad49)") (class "Default")
      (node (ref "U20") (pin "49") (pinfunction "TCK_49") (pintype "passive+no_connect"))
    )
    (net (code "76") (name "unconnected-(U20-TCN-Pad80)") (class "Default")
      (node (ref "U20") (pin "80") (pinfunction "TCN_80") (pintype "passive+no_connect"))
    )
    (net (code "77") (name "unconnected-(U20-TCP-Pad79)") (class "Default")
      (node (ref "U20") (pin "79") (pinfunction "TCP_79") (pintype "passive+no_connect"))
    )
    (net (code "78") (name "unconnected-(U20-TDI-Pad44)") (class "Default")
      (node (ref "U20") (pin "44") (pinfunction "TDI_44") (pintype "passive+no_connect"))
    )
    (net (code "79") (name "unconnected-(U20-TDO-Pad50)") (class "Default")
      (node (ref "U20") (pin "50") (pinfunction "TDO_50") (pintype "passive+no_connect"))
    )
    (net (code "80") (name "unconnected-(U20-TMS-Pad46)") (class "Default")
      (node (ref "U20") (pin "46") (pinfunction "TMS_46") (pintype "passive+no_connect"))
    )
    (net (code "81") (name "unconnected-(U20-TXN-Pad75)") (class "Default")
      (node (ref "U20") (pin "75") (pinfunction "TXN_75") (pintype "passive+no_connect"))
    )
    (net (code "82") (name "unconnected-(U20-TXP-Pad77)") (class "Default")
      (node (ref "U20") (pin "77") (pinfunction "TXP_77") (pintype "passive+no_connect"))
    )
    (net (code "83") (name "unconnected-(U20-XTAL2-Pad54)") (class "Default")
      (node (ref "U20") (pin "54") (pinfunction "XTAL2_54") (pintype "passive+no_connect"))
    )
  )
)
